# Laser_Driver_1.net
KiCad netlist of a schematic drawn in EAGLE
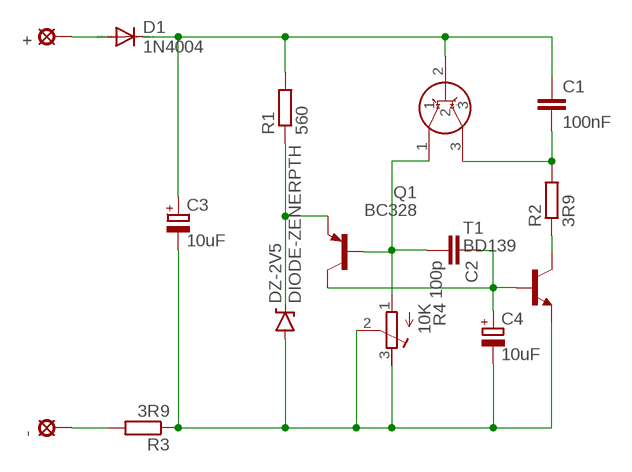
[diagram p0: schematic, sheet 1]

(export (version "E")
  (design (tool "Eeschema 10.0.6"))
  (components
    (comp (ref "+")
      (value "LSP10")
      (footprint "eagle-import:LSP10")
      (libsource (lib "eagle-import") (part "LSP10"))
    )
    (comp (ref "-")
      (value "LSP10")
      (footprint "eagle-import:LSP10")
      (libsource (lib "eagle-import") (part "LSP10"))
    )
    (comp (ref "C1")
      (value "100nF")
      (footprint "eagle-import:C5B5")
      (libsource (lib "eagle-import") (part "C5/5"))
    )
    (comp (ref "C2")
      (value "100p")
      (footprint "eagle-import:C5B5")
      (libsource (lib "eagle-import") (part "C5/5"))
    )
    (comp (ref "C3")
      (value "10uF")
      (footprint "eagle-import:E2,5-6E")
      (libsource (lib "eagle-import") (part "CPOL-EUE2,5-6E"))
    )
    (comp (ref "C4")
      (value "10uF")
      (footprint "eagle-import:E2,5-6E")
      (libsource (lib "eagle-import") (part "CPOL-EUE2,5-6E"))
    )
    (comp (ref "D1")
      (value "1N4004")
      (footprint "eagle-import:DO41-10")
      (libsource (lib "eagle-import") (part "1N4004"))
    )
    (comp (ref "DZ-2V5")
      (value "DIODE-ZENERPTH")
      (footprint "eagle-import:DIODE-ZENER")
      (libsource (lib "eagle-import") (part "DIODE-ZENERPTH"))
    )
    (comp (ref "LDIR_1")
      (value "LD_IR")
      (footprint "eagle-import:LASER_IR_TO18")
      (libsource (lib "eagle-import") (part "LD-IR-TO18"))
    )
    (comp (ref "Q1")
      (value "BC328")
      (footprint "eagle-import:TO92-EBC")
      (libsource (lib "eagle-import") (part "BC328"))
    )
    (comp (ref "R1")
      (value "560")
      (footprint "eagle-import:0207_7")
      (libsource (lib "eagle-import") (part "R-EU_0207/7"))
    )
    (comp (ref "R2")
      (value "3R9")
      (footprint "eagle-import:0207_7")
      (libsource (lib "eagle-import") (part "R-EU_0207/7"))
    )
    (comp (ref "R3")
      (value "3R9")
      (footprint "eagle-import:0207_7")
      (libsource (lib "eagle-import") (part "R-EU_0207/7"))
    )
    (comp (ref "R4")
      (value "10K")
      (footprint "eagle-import:RTRIM3339P")
      (libsource (lib "eagle-import") (part "R-TRIMM3339P"))
    )
    (comp (ref "T1")
      (value "BD139")
      (footprint "eagle-import:TO126")
      (libsource (lib "eagle-import") (part "BD139"))
    )
  )
  (nets
    (net (code "1") (name "Net-(+-PadMP)") (class "Default")
      (node (ref "+") (pin "MP") (pinfunction "MP_MP") (pintype "passive"))
      (node (ref "D1") (pin "A") (pinfunction "A_A") (pintype "passive"))
    )
    (net (code "2") (name "Net-(--PadMP)") (class "Default")
      (node (ref "-") (pin "MP") (pinfunction "MP_MP") (pintype "passive"))
      (node (ref "R3") (pin "2") (pinfunction "2_2") (pintype "passive"))
    )
    (net (code "3") (name "Net-(C1-Pad1)") (class "Default")
      (node (ref "C1") (pin "1") (pinfunction "1_1") (pintype "passive"))
      (node (ref "C3") (pin "+") (pinfunction "+_+") (pintype "passive"))
      (node (ref "D1") (pin "C") (pinfunction "C_C") (pintype "passive"))
      (node (ref "LDIR_1") (pin "2") (pinfunction "2_2") (pintype "bidirectional"))
      (node (ref "R1") (pin "2") (pinfunction "2_2") (pintype "passive"))
    )
    (net (code "4") (name "Net-(C1-Pad2)") (class "Default")
      (node (ref "C1") (pin "2") (pinfunction "2_2") (pintype "passive"))
      (node (ref "LDIR_1") (pin "3") (pinfunction "3_3") (pintype "bidirectional"))
      (node (ref "R2") (pin "2") (pinfunction "2_2") (pintype "passive"))
    )
    (net (code "5") (name "Net-(DZ-2V5-A)") (class "Default")
      (node (ref "C3") (pin "-") (pinfunction "-_-") (pintype "passive"))
      (node (ref "C4") (pin "-") (pinfunction "-_-") (pintype "passive"))
      (node (ref "DZ-2V5") (pin "P$2") (pinfunction "A_P$2") (pintype "passive"))
      (node (ref "R3") (pin "1") (pinfunction "1_1") (pintype "passive"))
      (node (ref "R4") (pin "2") (pinfunction "S_2") (pintype "passive"))
      (node (ref "R4") (pin "3") (pinfunction "E_3") (pintype "passive"))
      (node (ref "T1") (pin "1") (pinfunction "E_1") (pintype "passive"))
    )
    (net (code "6") (name "Net-(DZ-2V5-C)") (class "Default")
      (node (ref "DZ-2V5") (pin "P$1") (pinfunction "C_P$1") (pintype "passive"))
      (node (ref "Q1") (pin "E") (pinfunction "E_E") (pintype "passive"))
      (node (ref "R1") (pin "1") (pinfunction "1_1") (pintype "passive"))
    )
    (net (code "7") (name "Net-(R4-A)") (class "Default")
      (node (ref "C2") (pin "2") (pinfunction "2_2") (pintype "passive"))
      (node (ref "LDIR_1") (pin "1") (pinfunction "1_1") (pintype "bidirectional"))
      (node (ref "Q1") (pin "B") (pinfunction "B_B") (pintype "passive"))
      (node (ref "R4") (pin "1") (pinfunction "A_1") (pintype "passive"))
    )
    (net (code "8") (name "Net-(T1-B)") (class "Default")
      (node (ref "C2") (pin "1") (pinfunction "1_1") (pintype "passive"))
      (node (ref "C4") (pin "+") (pinfunction "+_+") (pintype "passive"))
      (node (ref "Q1") (pin "C") (pinfunction "C_C") (pintype "passive"))
      (node (ref "T1") (pin "3") (pinfunction "B_3") (pintype "passive"))
    )
    (net (code "9") (name "Net-(T1-C)") (class "Default")
      (node (ref "R2") (pin "1") (pinfunction "1_1") (pintype "passive"))
      (node (ref "T1") (pin "2") (pinfunction "C_2") (pintype "passive"))
    )
  )
)
